# v1.net
KiCad netlist of a schematic drawn in EAGLE
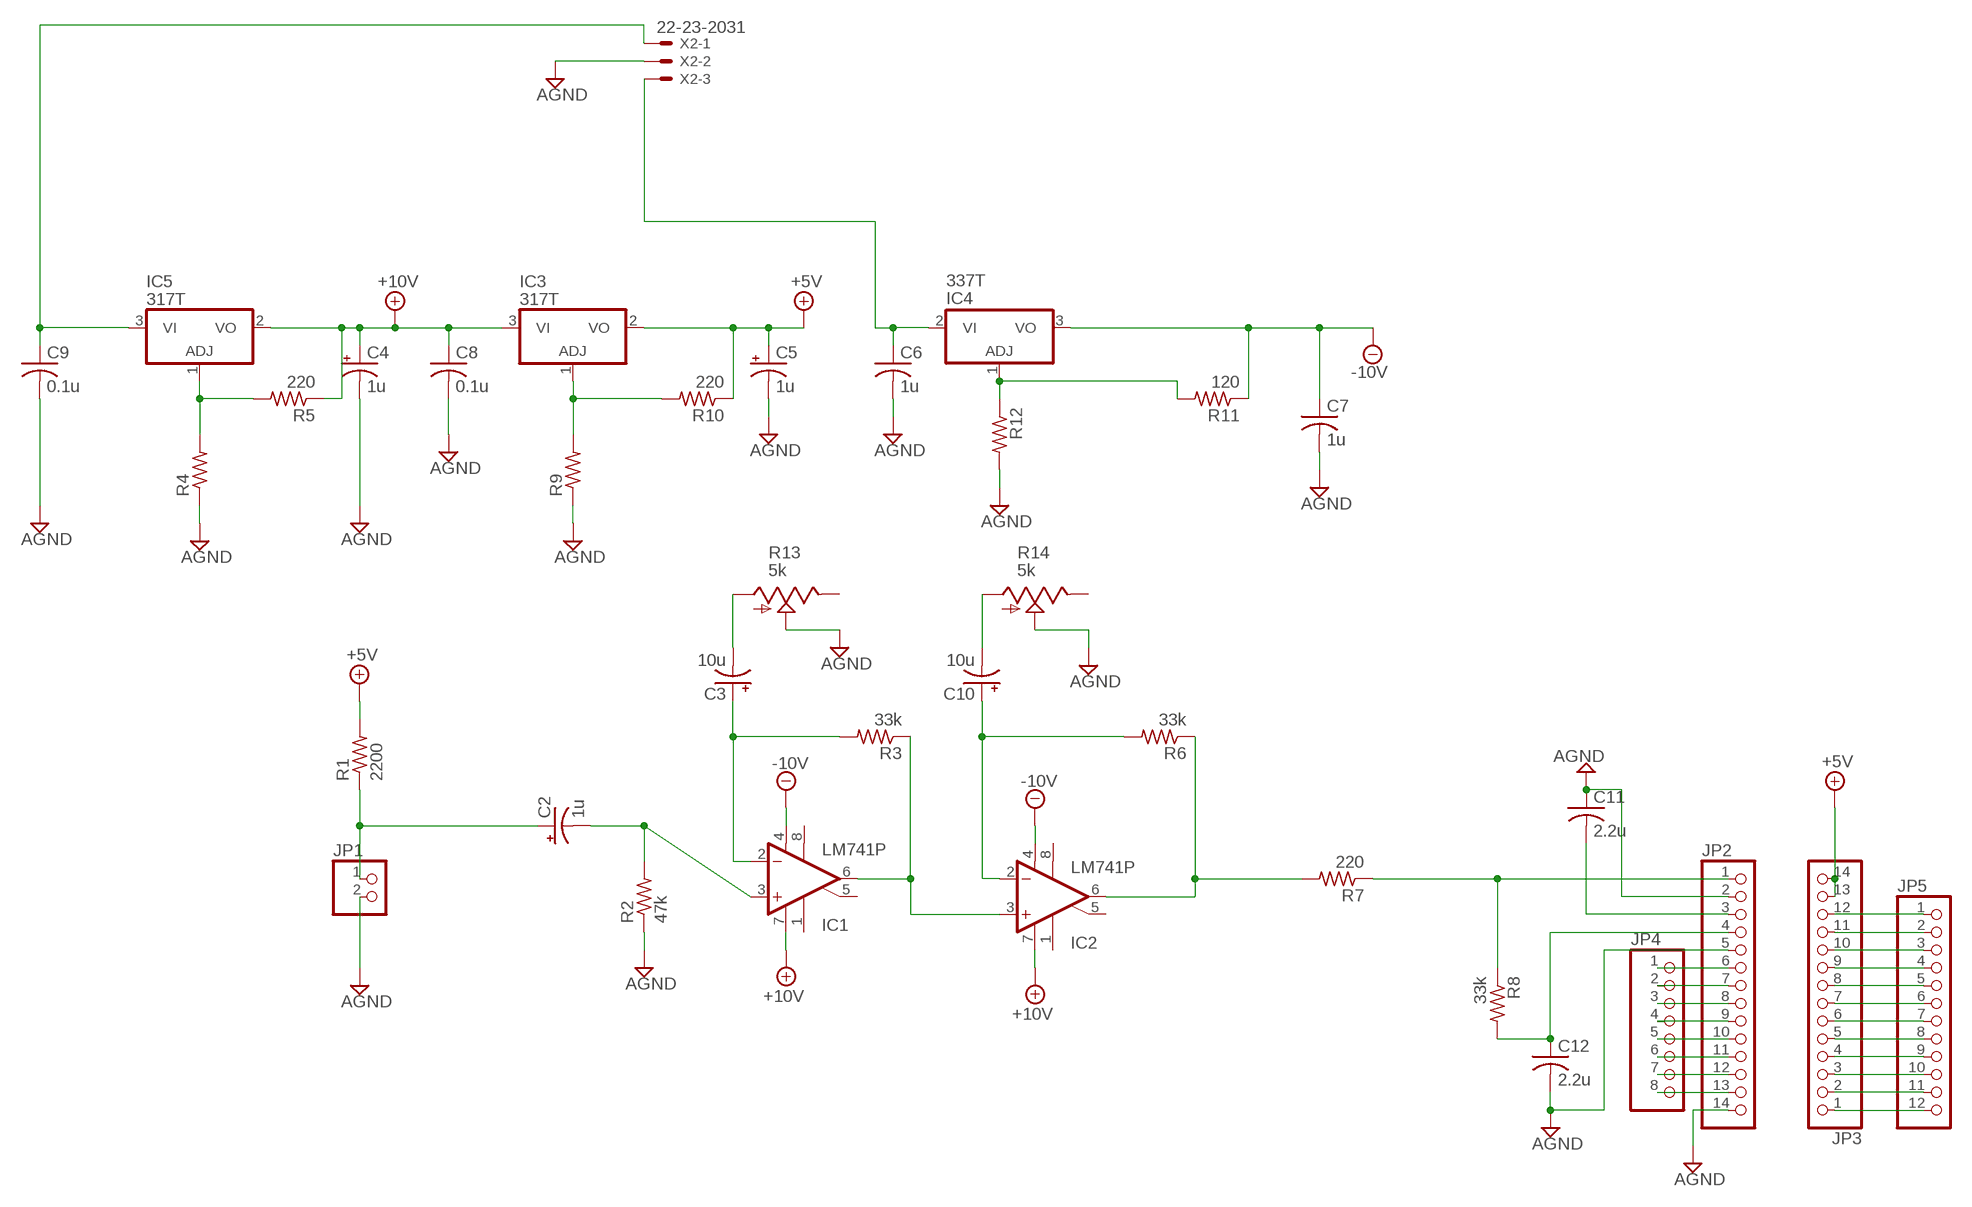
[diagram p0: schematic, sheet 1]

(export (version "E")
  (design (tool "Eeschema 10.0.6"))
  (components
    (comp (ref "C2")
      (value "1u")
      (footprint "eagle-import:E2,5-5")
      (libsource (lib "eagle-import") (part "CPOL-USE2.5-5"))
    )
    (comp (ref "C3")
      (value "10u")
      (footprint "eagle-import:E2,5-5")
      (libsource (lib "eagle-import") (part "CPOL-USE2.5-5"))
    )
    (comp (ref "C4")
      (value "1u")
      (footprint "eagle-import:E2,5-5")
      (libsource (lib "eagle-import") (part "CPOL-USE2.5-5"))
    )
    (comp (ref "C5")
      (value "1u")
      (footprint "eagle-import:E2,5-5")
      (libsource (lib "eagle-import") (part "CPOL-USE2.5-5"))
    )
    (comp (ref "C6")
      (value "1u")
      (footprint "eagle-import:C050-045X075")
      (libsource (lib "eagle-import") (part "C-US050-045X075"))
    )
    (comp (ref "C7")
      (value "1u")
      (footprint "eagle-import:C050-045X075")
      (libsource (lib "eagle-import") (part "C-US050-045X075"))
    )
    (comp (ref "C8")
      (value "0.1u")
      (footprint "eagle-import:C050-045X075")
      (libsource (lib "eagle-import") (part "C-US050-045X075"))
    )
    (comp (ref "C9")
      (value "0.1u")
      (footprint "eagle-import:C050-045X075")
      (libsource (lib "eagle-import") (part "C-US050-045X075"))
    )
    (comp (ref "C10")
      (value "10u")
      (footprint "eagle-import:E2,5-5")
      (libsource (lib "eagle-import") (part "CPOL-USE2.5-5"))
    )
    (comp (ref "C11")
      (value "2.2u")
      (footprint "eagle-import:C050-045X075")
      (libsource (lib "eagle-import") (part "C-US050-045X075"))
    )
    (comp (ref "C12")
      (value "2.2u")
      (footprint "eagle-import:C050-045X075")
      (libsource (lib "eagle-import") (part "C-US050-045X075"))
    )
    (comp (ref "IC1")
      (value "LM741P")
      (footprint "eagle-import:DIL08")
      (libsource (lib "eagle-import") (part "741PLM"))
    )
    (comp (ref "IC2")
      (value "LM741P")
      (footprint "eagle-import:DIL08")
      (libsource (lib "eagle-import") (part "741PLM"))
    )
    (comp (ref "IC3")
      (value "317T")
      (footprint "eagle-import:TO220H")
      (libsource (lib "eagle-import") (part "317T"))
    )
    (comp (ref "IC4")
      (value "337T")
      (footprint "eagle-import:TO220H")
      (libsource (lib "eagle-import") (part "337T"))
    )
    (comp (ref "IC5")
      (value "317T")
      (footprint "eagle-import:TO220H")
      (libsource (lib "eagle-import") (part "317T"))
    )
    (comp (ref "JP1")
      (value "PINHD-1X2")
      (footprint "eagle-import:1X02")
      (libsource (lib "eagle-import") (part "PINHD-1X2"))
    )
    (comp (ref "JP2")
      (value "PINHD-1X14")
      (footprint "eagle-import:1X14")
      (libsource (lib "eagle-import") (part "PINHD-1X14"))
    )
    (comp (ref "JP3")
      (value "PINHD-1X14")
      (footprint "eagle-import:1X14")
      (libsource (lib "eagle-import") (part "PINHD-1X14"))
    )
    (comp (ref "JP4")
      (value "PINHD-1X8")
      (footprint "eagle-import:1X08")
      (libsource (lib "eagle-import") (part "PINHD-1X8"))
    )
    (comp (ref "JP5")
      (value "PINHD-1X12")
      (footprint "eagle-import:1X12")
      (libsource (lib "eagle-import") (part "PINHD-1X12"))
    )
    (comp (ref "R1")
      (value "2200")
      (footprint "eagle-import:0207_10")
      (libsource (lib "eagle-import") (part "R-US_0207/10"))
    )
    (comp (ref "R2")
      (value "47k")
      (footprint "eagle-import:0207_10")
      (libsource (lib "eagle-import") (part "R-US_0207/10"))
    )
    (comp (ref "R3")
      (value "33k")
      (footprint "eagle-import:0207_10")
      (libsource (lib "eagle-import") (part "R-US_0207/10"))
    )
    (comp (ref "R4")
      (value "R-US_0207/10")
      (footprint "eagle-import:0207_10")
      (libsource (lib "eagle-import") (part "R-US_0207/10"))
    )
    (comp (ref "R5")
      (value "220")
      (footprint "eagle-import:0207_10")
      (libsource (lib "eagle-import") (part "R-US_0207/10"))
    )
    (comp (ref "R6")
      (value "33k")
      (footprint "eagle-import:0207_10")
      (libsource (lib "eagle-import") (part "R-US_0207/10"))
    )
    (comp (ref "R7")
      (value "220")
      (footprint "eagle-import:0207_10")
      (libsource (lib "eagle-import") (part "R-US_0207/10"))
    )
    (comp (ref "R8")
      (value "33k")
      (footprint "eagle-import:0207_10")
      (libsource (lib "eagle-import") (part "R-US_0207/10"))
    )
    (comp (ref "R9")
      (value "R-US_0207/10")
      (footprint "eagle-import:0207_10")
      (libsource (lib "eagle-import") (part "R-US_0207/10"))
    )
    (comp (ref "R10")
      (value "220")
      (footprint "eagle-import:0207_10")
      (libsource (lib "eagle-import") (part "R-US_0207/10"))
    )
    (comp (ref "R11")
      (value "120")
      (footprint "eagle-import:0207_10")
      (libsource (lib "eagle-import") (part "R-US_0207/10"))
    )
    (comp (ref "R12")
      (value "R-US_0207/10")
      (footprint "eagle-import:0207_10")
      (libsource (lib "eagle-import") (part "R-US_0207/10"))
    )
    (comp (ref "R13")
      (value "5k")
      (footprint "eagle-import:CA6V")
      (libsource (lib "eagle-import") (part "TRIM_US-CA6V"))
    )
    (comp (ref "R14")
      (value "5k")
      (footprint "eagle-import:CA6V")
      (libsource (lib "eagle-import") (part "TRIM_US-CA6V"))
    )
    (comp (ref "X2")
      (value "22-23-2031")
      (footprint "eagle-import:22-23-2031")
      (fields (field (name "MF") "MOLEX"))
      (libsource (lib "eagle-import") (part "22-23-2031"))
    )
  )
  (nets
    (net (code "1") (name "+5V") (class "Default")
      (node (ref "C5") (pin "+") (pinfunction "+_+") (pintype "passive"))
      (node (ref "IC3") (pin "2") (pinfunction "VO_2") (pintype "passive"))
      (node (ref "JP3") (pin "13") (pinfunction "13_13") (pintype "passive"))
      (node (ref "JP3") (pin "14") (pinfunction "14_14") (pintype "passive"))
      (node (ref "R1") (pin "2") (pinfunction "2_2") (pintype "passive"))
      (node (ref "R10") (pin "1") (pinfunction "1_1") (pintype "passive"))
    )
    (net (code "2") (name "+10V") (class "Default")
      (node (ref "C4") (pin "+") (pinfunction "+_+") (pintype "passive"))
      (node (ref "C8") (pin "1") (pinfunction "1_1") (pintype "passive"))
      (node (ref "IC1") (pin "7") (pinfunction "V+_7") (pintype "power_in"))
      (node (ref "IC2") (pin "7") (pinfunction "V+_7") (pintype "power_in"))
      (node (ref "IC3") (pin "3") (pinfunction "VI_3") (pintype "input"))
      (node (ref "IC5") (pin "2") (pinfunction "VO_2") (pintype "passive"))
      (node (ref "R5") (pin "1") (pinfunction "1_1") (pintype "passive"))
    )
    (net (code "3") (name "-10V") (class "Default")
      (node (ref "C7") (pin "1") (pinfunction "1_1") (pintype "passive"))
      (node (ref "IC1") (pin "4") (pinfunction "V-_4") (pintype "power_in"))
      (node (ref "IC2") (pin "4") (pinfunction "V-_4") (pintype "power_in"))
      (node (ref "IC4") (pin "3") (pinfunction "VO_3") (pintype "passive"))
      (node (ref "R11") (pin "1") (pinfunction "1_1") (pintype "passive"))
    )
    (net (code "4") (name "AGND") (class "Default")
      (node (ref "C11") (pin "1") (pinfunction "1_1") (pintype "passive"))
      (node (ref "C12") (pin "2") (pinfunction "2_2") (pintype "passive"))
      (node (ref "C4") (pin "-") (pinfunction "-_-") (pintype "passive"))
      (node (ref "C5") (pin "-") (pinfunction "-_-") (pintype "passive"))
      (node (ref "C6") (pin "2") (pinfunction "2_2") (pintype "passive"))
      (node (ref "C7") (pin "2") (pinfunction "2_2") (pintype "passive"))
      (node (ref "C8") (pin "2") (pinfunction "2_2") (pintype "passive"))
      (node (ref "C9") (pin "2") (pinfunction "2_2") (pintype "passive"))
      (node (ref "JP1") (pin "2") (pinfunction "2_2") (pintype "passive"))
      (node (ref "JP2") (pin "14") (pinfunction "14_14") (pintype "passive"))
      (node (ref "JP2") (pin "2") (pinfunction "2_2") (pintype "passive"))
      (node (ref "JP2") (pin "5") (pinfunction "5_5") (pintype "passive"))
      (node (ref "R12") (pin "2") (pinfunction "2_2") (pintype "passive"))
      (node (ref "R13") (pin "S") (pinfunction "S_S") (pintype "passive"))
      (node (ref "R14") (pin "S") (pinfunction "S_S") (pintype "passive"))
      (node (ref "R2") (pin "1") (pinfunction "1_1") (pintype "passive"))
      (node (ref "R4") (pin "1") (pinfunction "1_1") (pintype "passive"))
      (node (ref "R9") (pin "1") (pinfunction "1_1") (pintype "passive"))
      (node (ref "X2") (pin "2") (pinfunction "S_2") (pintype "passive"))
    )
    (net (code "5") (name "Net-(C2-Pad+)") (class "Default")
      (node (ref "C2") (pin "+") (pinfunction "+_+") (pintype "passive"))
      (node (ref "JP1") (pin "1") (pinfunction "1_1") (pintype "passive"))
      (node (ref "R1") (pin "1") (pinfunction "1_1") (pintype "passive"))
    )
    (net (code "6") (name "Net-(C3-Pad-)") (class "Default")
      (node (ref "C3") (pin "-") (pinfunction "-_-") (pintype "passive"))
      (node (ref "R13") (pin "A") (pinfunction "A_A") (pintype "passive"))
    )
    (net (code "7") (name "Net-(C10-Pad-)") (class "Default")
      (node (ref "C10") (pin "-") (pinfunction "-_-") (pintype "passive"))
      (node (ref "R14") (pin "A") (pinfunction "A_A") (pintype "passive"))
    )
    (net (code "8") (name "Net-(C11-Pad2)") (class "Default")
      (node (ref "C11") (pin "2") (pinfunction "2_2") (pintype "passive"))
      (node (ref "JP2") (pin "3") (pinfunction "3_3") (pintype "passive"))
    )
    (net (code "9") (name "Net-(C12-Pad1)") (class "Default")
      (node (ref "C12") (pin "1") (pinfunction "1_1") (pintype "passive"))
      (node (ref "JP2") (pin "4") (pinfunction "4_4") (pintype "passive"))
      (node (ref "R8") (pin "2") (pinfunction "2_2") (pintype "passive"))
    )
    (net (code "10") (name "Net-(IC1-+IN)") (class "Default")
      (node (ref "C2") (pin "-") (pinfunction "-_-") (pintype "passive"))
      (node (ref "IC1") (pin "3") (pinfunction "+IN_3") (pintype "input"))
      (node (ref "R2") (pin "2") (pinfunction "2_2") (pintype "passive"))
    )
    (net (code "11") (name "Net-(IC1--IN)") (class "Default")
      (node (ref "C3") (pin "+") (pinfunction "+_+") (pintype "passive"))
      (node (ref "IC1") (pin "2") (pinfunction "-IN_2") (pintype "input"))
      (node (ref "R3") (pin "2") (pinfunction "2_2") (pintype "passive"))
    )
    (net (code "12") (name "Net-(IC1-OUT)") (class "Default")
      (node (ref "IC1") (pin "6") (pinfunction "OUT_6") (pintype "output"))
      (node (ref "IC2") (pin "3") (pinfunction "+IN_3") (pintype "input"))
      (node (ref "R3") (pin "1") (pinfunction "1_1") (pintype "passive"))
    )
    (net (code "13") (name "Net-(IC2--IN)") (class "Default")
      (node (ref "C10") (pin "+") (pinfunction "+_+") (pintype "passive"))
      (node (ref "IC2") (pin "2") (pinfunction "-IN_2") (pintype "input"))
      (node (ref "R6") (pin "2") (pinfunction "2_2") (pintype "passive"))
    )
    (net (code "14") (name "Net-(IC2-OUT)") (class "Default")
      (node (ref "IC2") (pin "6") (pinfunction "OUT_6") (pintype "output"))
      (node (ref "R6") (pin "1") (pinfunction "1_1") (pintype "passive"))
      (node (ref "R7") (pin "2") (pinfunction "2_2") (pintype "passive"))
    )
    (net (code "15") (name "Net-(IC3-ADJ)") (class "Default")
      (node (ref "IC3") (pin "1") (pinfunction "ADJ_1") (pintype "input"))
      (node (ref "R10") (pin "2") (pinfunction "2_2") (pintype "passive"))
      (node (ref "R9") (pin "2") (pinfunction "2_2") (pintype "passive"))
    )
    (net (code "16") (name "Net-(IC4-ADJ)") (class "Default")
      (node (ref "IC4") (pin "1") (pinfunction "ADJ_1") (pintype "input"))
      (node (ref "R11") (pin "2") (pinfunction "2_2") (pintype "passive"))
      (node (ref "R12") (pin "1") (pinfunction "1_1") (pintype "passive"))
    )
    (net (code "17") (name "Net-(IC4-VI)") (class "Default")
      (node (ref "C6") (pin "1") (pinfunction "1_1") (pintype "passive"))
      (node (ref "IC4") (pin "2") (pinfunction "VI_2") (pintype "input"))
      (node (ref "X2") (pin "3") (pinfunction "S_3") (pintype "passive"))
    )
    (net (code "18") (name "Net-(IC5-ADJ)") (class "Default")
      (node (ref "IC5") (pin "1") (pinfunction "ADJ_1") (pintype "input"))
      (node (ref "R4") (pin "2") (pinfunction "2_2") (pintype "passive"))
      (node (ref "R5") (pin "2") (pinfunction "2_2") (pintype "passive"))
    )
    (net (code "19") (name "Net-(IC5-VI)") (class "Default")
      (node (ref "C9") (pin "1") (pinfunction "1_1") (pintype "passive"))
      (node (ref "IC5") (pin "3") (pinfunction "VI_3") (pintype "input"))
      (node (ref "X2") (pin "1") (pinfunction "S_1") (pintype "passive"))
    )
    (net (code "20") (name "Net-(JP2-Pad1)") (class "Default")
      (node (ref "JP2") (pin "1") (pinfunction "1_1") (pintype "passive"))
      (node (ref "R7") (pin "1") (pinfunction "1_1") (pintype "passive"))
      (node (ref "R8") (pin "1") (pinfunction "1_1") (pintype "passive"))
    )
    (net (code "21") (name "Net-(JP2-Pad6)") (class "Default")
      (node (ref "JP2") (pin "6") (pinfunction "6_6") (pintype "passive"))
      (node (ref "JP4") (pin "1") (pinfunction "1_1") (pintype "passive"))
    )
    (net (code "22") (name "Net-(JP2-Pad7)") (class "Default")
      (node (ref "JP2") (pin "7") (pinfunction "7_7") (pintype "passive"))
      (node (ref "JP4") (pin "2") (pinfunction "2_2") (pintype "passive"))
    )
    (net (code "23") (name "Net-(JP2-Pad8)") (class "Default")
      (node (ref "JP2") (pin "8") (pinfunction "8_8") (pintype "passive"))
      (node (ref "JP4") (pin "3") (pinfunction "3_3") (pintype "passive"))
    )
    (net (code "24") (name "Net-(JP2-Pad9)") (class "Default")
      (node (ref "JP2") (pin "9") (pinfunction "9_9") (pintype "passive"))
      (node (ref "JP4") (pin "4") (pinfunction "4_4") (pintype "passive"))
    )
    (net (code "25") (name "Net-(JP2-Pad10)") (class "Default")
      (node (ref "JP2") (pin "10") (pinfunction "10_10") (pintype "passive"))
      (node (ref "JP4") (pin "5") (pinfunction "5_5") (pintype "passive"))
    )
    (net (code "26") (name "Net-(JP2-Pad11)") (class "Default")
      (node (ref "JP2") (pin "11") (pinfunction "11_11") (pintype "passive"))
      (node (ref "JP4") (pin "6") (pinfunction "6_6") (pintype "passive"))
    )
    (net (code "27") (name "Net-(JP2-Pad12)") (class "Default")
      (node (ref "JP2") (pin "12") (pinfunction "12_12") (pintype "passive"))
      (node (ref "JP4") (pin "7") (pinfunction "7_7") (pintype "passive"))
    )
    (net (code "28") (name "Net-(JP2-Pad13)") (class "Default")
      (node (ref "JP2") (pin "13") (pinfunction "13_13") (pintype "passive"))
      (node (ref "JP4") (pin "8") (pinfunction "8_8") (pintype "passive"))
    )
    (net (code "29") (name "Net-(JP3-Pad1)") (class "Default")
      (node (ref "JP3") (pin "1") (pinfunction "1_1") (pintype "passive"))
      (node (ref "JP5") (pin "12") (pinfunction "12_12") (pintype "passive"))
    )
    (net (code "30") (name "Net-(JP3-Pad2)") (class "Default")
      (node (ref "JP3") (pin "2") (pinfunction "2_2") (pintype "passive"))
      (node (ref "JP5") (pin "11") (pinfunction "11_11") (pintype "passive"))
    )
    (net (code "31") (name "Net-(JP3-Pad3)") (class "Default")
      (node (ref "JP3") (pin "3") (pinfunction "3_3") (pintype "passive"))
      (node (ref "JP5") (pin "10") (pinfunction "10_10") (pintype "passive"))
    )
    (net (code "32") (name "Net-(JP3-Pad4)") (class "Default")
      (node (ref "JP3") (pin "4") (pinfunction "4_4") (pintype "passive"))
      (node (ref "JP5") (pin "9") (pinfunction "9_9") (pintype "passive"))
    )
    (net (code "33") (name "Net-(JP3-Pad5)") (class "Default")
      (node (ref "JP3") (pin "5") (pinfunction "5_5") (pintype "passive"))
      (node (ref "JP5") (pin "8") (pinfunction "8_8") (pintype "passive"))
    )
    (net (code "34") (name "Net-(JP3-Pad6)") (class "Default")
      (node (ref "JP3") (pin "6") (pinfunction "6_6") (pintype "passive"))
      (node (ref "JP5") (pin "7") (pinfunction "7_7") (pintype "passive"))
    )
    (net (code "35") (name "Net-(JP3-Pad7)") (class "Default")
      (node (ref "JP3") (pin "7") (pinfunction "7_7") (pintype "passive"))
      (node (ref "JP5") (pin "6") (pinfunction "6_6") (pintype "passive"))
    )
    (net (code "36") (name "Net-(JP3-Pad8)") (class "Default")
      (node (ref "JP3") (pin "8") (pinfunction "8_8") (pintype "passive"))
      (node (ref "JP5") (pin "5") (pinfunction "5_5") (pintype "passive"))
    )
    (net (code "37") (name "Net-(JP3-Pad9)") (class "Default")
      (node (ref "JP3") (pin "9") (pinfunction "9_9") (pintype "passive"))
      (node (ref "JP5") (pin "4") (pinfunction "4_4") (pintype "passive"))
    )
    (net (code "38") (name "Net-(JP3-Pad10)") (class "Default")
      (node (ref "JP3") (pin "10") (pinfunction "10_10") (pintype "passive"))
      (node (ref "JP5") (pin "3") (pinfunction "3_3") (pintype "passive"))
    )
    (net (code "39") (name "Net-(JP3-Pad11)") (class "Default")
      (node (ref "JP3") (pin "11") (pinfunction "11_11") (pintype "passive"))
      (node (ref "JP5") (pin "2") (pinfunction "2_2") (pintype "passive"))
    )
    (net (code "40") (name "Net-(JP3-Pad12)") (class "Default")
      (node (ref "JP3") (pin "12") (pinfunction "12_12") (pintype "passive"))
      (node (ref "JP5") (pin "1") (pinfunction "1_1") (pintype "passive"))
    )
    (net (code "41") (name "unconnected-(IC1-ON1-Pad1)") (class "Default")
      (node (ref "IC1") (pin "1") (pinfunction "ON1_1") (pintype "passive"))
    )
    (net (code "42") (name "unconnected-(IC1-ON2-Pad5)") (class "Default")
      (node (ref "IC1") (pin "5") (pinfunction "ON2_5") (pintype "passive"))
    )
    (net (code "43") (name "unconnected-(IC1-OPT-Pad8)") (class "Default")
      (node (ref "IC1") (pin "8") (pinfunction "OPT_8") (pintype "passive"))
    )
    (net (code "44") (name "unconnected-(IC2-ON1-Pad1)") (class "Default")
      (node (ref "IC2") (pin "1") (pinfunction "ON1_1") (pintype "passive"))
    )
    (net (code "45") (name "unconnected-(IC2-ON2-Pad5)") (class "Default")
      (node (ref "IC2") (pin "5") (pinfunction "ON2_5") (pintype "passive"))
    )
    (net (code "46") (name "unconnected-(IC2-OPT-Pad8)") (class "Default")
      (node (ref "IC2") (pin "8") (pinfunction "OPT_8") (pintype "passive"))
    )
    (net (code "47") (name "unconnected-(R13-PadE)") (class "Default")
      (node (ref "R13") (pin "E") (pinfunction "E_E") (pintype "passive"))
    )
    (net (code "48") (name "unconnected-(R14-PadE)") (class "Default")
      (node (ref "R14") (pin "E") (pinfunction "E_E") (pintype "passive"))
    )
  )
)
